# 04_EEPROM_FLASH.net
KiCad netlist of a schematic drawn in Altium Designer
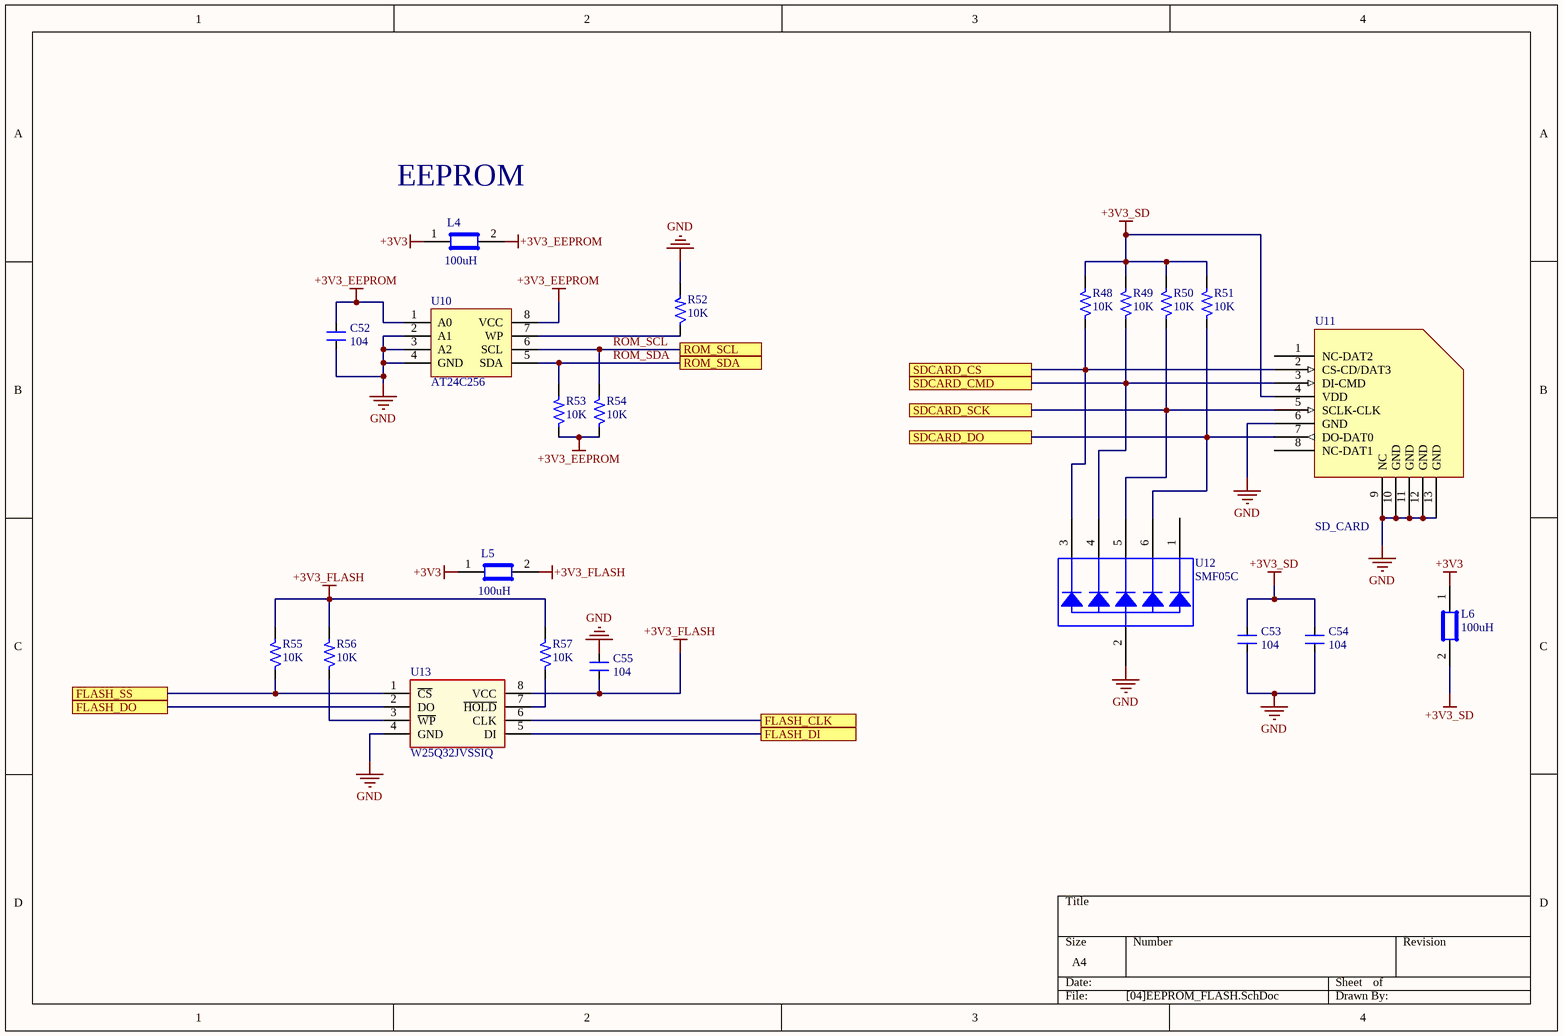
[diagram p0: [04]EEPROM_FLASH.SchDoc]

(export (version "E")
  (design (tool "Eeschema 10.0.6"))
  (components
    (comp (ref "C52")
      (value "104")
      (footprint "C0603 SMT")
      (description "Cap SMD")
      (libsource (lib "GPS_Traking_V1_1") (part "CM"))
    )
    (comp (ref "C53")
      (value "104")
      (footprint "C0603 SMT")
      (description "Cap SMD")
      (libsource (lib "GPS_Traking_V1_1") (part "CM"))
    )
    (comp (ref "C54")
      (value "104")
      (footprint "C0603 SMT")
      (description "Cap SMD")
      (libsource (lib "GPS_Traking_V1_1") (part "CM"))
    )
    (comp (ref "C55")
      (value "104")
      (footprint "C0603 SMT")
      (description "Cap SMD")
      (libsource (lib "GPS_Traking_V1_1") (part "CM"))
    )
    (comp (ref "L4")
      (value "100uH")
      (footprint "R0805")
      (description "100uH 0805")
      (libsource (lib "GPS_Traking_V1_1") (part "Ferrite Bead"))
    )
    (comp (ref "L5")
      (value "100uH")
      (footprint "R0805")
      (description "100uH 0805")
      (libsource (lib "GPS_Traking_V1_1") (part "Ferrite Bead"))
    )
    (comp (ref "L6")
      (value "100uH")
      (footprint "R0805")
      (description "100uH 0805")
      (libsource (lib "GPS_Traking_V1_1") (part "Ferrite Bead"))
    )
    (comp (ref "R48")
      (value "10K")
      (footprint "R0603 -SMT")
      (description "Resistor SMD")
      (libsource (lib "GPS_Traking_V1_1") (part "RM"))
    )
    (comp (ref "R49")
      (value "10K")
      (footprint "R0603 -SMT")
      (description "Resistor SMD")
      (libsource (lib "GPS_Traking_V1_1") (part "RM"))
    )
    (comp (ref "R50")
      (value "10K")
      (footprint "R0603 -SMT")
      (description "Resistor SMD")
      (libsource (lib "GPS_Traking_V1_1") (part "RM"))
    )
    (comp (ref "R51")
      (value "10K")
      (footprint "R0603 -SMT")
      (description "Resistor SMD")
      (libsource (lib "GPS_Traking_V1_1") (part "RM"))
    )
    (comp (ref "R52")
      (value "10K")
      (footprint "R0603 -SMT")
      (description "Resistor SMD")
      (libsource (lib "GPS_Traking_V1_1") (part "RM"))
    )
    (comp (ref "R53")
      (value "10K")
      (footprint "R0603 -SMT")
      (description "Resistor SMD")
      (libsource (lib "GPS_Traking_V1_1") (part "RM"))
    )
    (comp (ref "R54")
      (value "10K")
      (footprint "R0603 -SMT")
      (description "Resistor SMD")
      (libsource (lib "GPS_Traking_V1_1") (part "RM"))
    )
    (comp (ref "R55")
      (value "10K")
      (footprint "R0603 -SMT")
      (description "Resistor SMD")
      (libsource (lib "GPS_Traking_V1_1") (part "RM"))
    )
    (comp (ref "R56")
      (value "10K")
      (footprint "R0603 -SMT")
      (description "Resistor SMD")
      (libsource (lib "GPS_Traking_V1_1") (part "RM"))
    )
    (comp (ref "R57")
      (value "10K")
      (footprint "R0603 -SMT")
      (description "Resistor SMD")
      (libsource (lib "GPS_Traking_V1_1") (part "RM"))
    )
    (comp (ref "U10")
      (value "AT24C256")
      (footprint "SO-8")
      (libsource (lib "GPS_Traking_V1_1") (part "AT24Cxx"))
    )
    (comp (ref "U11")
      (value "SD_CARD")
      (footprint "MICROSD2")
      (description "SD/MMC holder")
      (libsource (lib "My Library") (part "MicroSD"))
    )
    (comp (ref "U12")
      (value "SMF05C")
      (footprint "SOT_363_6")
      (description "ESD Protection")
      (libsource (lib "GPS_Traking_V1_1") (part "SMF05C"))
    )
    (comp (ref "U13")
      (value "W25Q32JVSSIQ")
      (footprint "SO-8 208")
      (description "FLASH 32MBIT 133MHZ 8SOP")
      (libsource (lib "GPS_Traking_V1_1") (part "W25Q32JV"))
    )
  )
  (nets
    (net (code "1") (name "+3V3") (class "Default")
      (node (ref "L4") (pin "1") (pinfunction "1_1") (pintype "passive"))
      (node (ref "L5") (pin "1") (pinfunction "1_1") (pintype "passive"))
      (node (ref "L6") (pin "1") (pinfunction "1_1") (pintype "passive"))
    )
    (net (code "2") (name "+3V3_EEPROM") (class "Default")
      (node (ref "C52") (pin "2") (pinfunction "2_2") (pintype "passive"))
      (node (ref "L4") (pin "2") (pinfunction "2_2") (pintype "passive"))
      (node (ref "R53") (pin "1") (pinfunction "1_1") (pintype "passive"))
      (node (ref "R54") (pin "1") (pinfunction "1_1") (pintype "passive"))
      (node (ref "U10") (pin "1") (pinfunction "A0_1") (pintype "passive"))
      (node (ref "U10") (pin "8") (pinfunction "VCC_8") (pintype "passive"))
    )
    (net (code "3") (name "+3V3_FLASH") (class "Default")
      (node (ref "C55") (pin "1") (pinfunction "1_1") (pintype "passive"))
      (node (ref "L5") (pin "2") (pinfunction "2_2") (pintype "passive"))
      (node (ref "R55") (pin "2") (pinfunction "2_2") (pintype "passive"))
      (node (ref "R56") (pin "2") (pinfunction "2_2") (pintype "passive"))
      (node (ref "R57") (pin "2") (pinfunction "2_2") (pintype "passive"))
      (node (ref "U13") (pin "8") (pinfunction "VCC_8") (pintype "passive"))
    )
    (net (code "4") (name "+3V3_SD") (class "Default")
      (node (ref "C53") (pin "2") (pinfunction "2_2") (pintype "passive"))
      (node (ref "C54") (pin "2") (pinfunction "2_2") (pintype "passive"))
      (node (ref "L6") (pin "2") (pinfunction "2_2") (pintype "passive"))
      (node (ref "R48") (pin "2") (pinfunction "2_2") (pintype "passive"))
      (node (ref "R49") (pin "2") (pinfunction "2_2") (pintype "passive"))
      (node (ref "R50") (pin "2") (pinfunction "2_2") (pintype "passive"))
      (node (ref "R51") (pin "2") (pinfunction "2_2") (pintype "passive"))
      (node (ref "U11") (pin "4") (pinfunction "VDD_4") (pintype "passive"))
    )
    (net (code "5") (name "/FLASH_CLK") (class "Default")
      (node (ref "U13") (pin "6") (pinfunction "CLK_6") (pintype "passive"))
    )
    (net (code "6") (name "/FLASH_DI") (class "Default")
      (node (ref "U13") (pin "5") (pinfunction "DI_5") (pintype "passive"))
    )
    (net (code "7") (name "/FLASH_DO") (class "Default")
      (node (ref "U13") (pin "2") (pinfunction "DO_2") (pintype "passive"))
    )
    (net (code "8") (name "/FLASH_SS") (class "Default")
      (node (ref "R55") (pin "1") (pinfunction "1_1") (pintype "passive"))
      (node (ref "U13") (pin "1") (pinfunction "~{CS}_1") (pintype "passive"))
    )
    (net (code "9") (name "/ROM_SCL") (class "Default")
      (node (ref "R54") (pin "2") (pinfunction "2_2") (pintype "passive"))
      (node (ref "U10") (pin "6") (pinfunction "SCL_6") (pintype "passive"))
    )
    (net (code "10") (name "/ROM_SDA") (class "Default")
      (node (ref "R53") (pin "2") (pinfunction "2_2") (pintype "passive"))
      (node (ref "U10") (pin "5") (pinfunction "SDA_5") (pintype "passive"))
    )
    (net (code "11") (name "/SDCARD_CMD") (class "Default")
      (node (ref "R49") (pin "1") (pinfunction "1_1") (pintype "passive"))
      (node (ref "U11") (pin "3") (pinfunction "DI-CMD_3") (pintype "input"))
      (node (ref "U12") (pin "4") (pinfunction "K3_4") (pintype "passive"))
    )
    (net (code "12") (name "/SDCARD_CS") (class "Default")
      (node (ref "R48") (pin "1") (pinfunction "1_1") (pintype "passive"))
      (node (ref "U11") (pin "2") (pinfunction "CS-CD/DAT3_2") (pintype "input"))
      (node (ref "U12") (pin "3") (pinfunction "K2_3") (pintype "passive"))
    )
    (net (code "13") (name "/SDCARD_DO") (class "Default")
      (node (ref "R51") (pin "1") (pinfunction "1_1") (pintype "passive"))
      (node (ref "U11") (pin "7") (pinfunction "DO-DAT0_7") (pintype "output"))
      (node (ref "U12") (pin "6") (pinfunction "K5_6") (pintype "passive"))
    )
    (net (code "14") (name "/SDCARD_SCK") (class "Default")
      (node (ref "R50") (pin "1") (pinfunction "1_1") (pintype "passive"))
      (node (ref "U11") (pin "5") (pinfunction "SCLK-CLK_5") (pintype "input"))
      (node (ref "U12") (pin "5") (pinfunction "K4_5") (pintype "power_in"))
    )
    (net (code "15") (name "GND") (class "Default")
      (node (ref "C52") (pin "1") (pinfunction "1_1") (pintype "passive"))
      (node (ref "C53") (pin "1") (pinfunction "1_1") (pintype "passive"))
      (node (ref "C54") (pin "1") (pinfunction "1_1") (pintype "passive"))
      (node (ref "C55") (pin "2") (pinfunction "2_2") (pintype "passive"))
      (node (ref "R52") (pin "2") (pinfunction "2_2") (pintype "passive"))
      (node (ref "U10") (pin "2") (pinfunction "A1_2") (pintype "passive"))
      (node (ref "U10") (pin "3") (pinfunction "A2_3") (pintype "passive"))
      (node (ref "U10") (pin "4") (pinfunction "GND_4") (pintype "passive"))
      (node (ref "U11") (pin "10") (pinfunction "GND_10") (pintype "passive"))
      (node (ref "U11") (pin "11") (pinfunction "GND_11") (pintype "passive"))
      (node (ref "U11") (pin "12") (pinfunction "GND_12") (pintype "passive"))
      (node (ref "U11") (pin "13") (pinfunction "GND_13") (pintype "passive"))
      (node (ref "U11") (pin "6") (pinfunction "GND_6") (pintype "passive"))
      (node (ref "U11") (pin "9") (pinfunction "NC_9") (pintype "passive"))
      (node (ref "U12") (pin "2") (pinfunction "A_2") (pintype "power_in"))
      (node (ref "U13") (pin "4") (pinfunction "GND_4") (pintype "passive"))
    )
    (net (code "16") (name "Net-(U10-WP)") (class "Default")
      (node (ref "R52") (pin "1") (pinfunction "1_1") (pintype "passive"))
      (node (ref "U10") (pin "7") (pinfunction "WP_7") (pintype "passive"))
    )
    (net (code "17") (name "Net-(U13-~{HOLD})") (class "Default")
      (node (ref "R57") (pin "1") (pinfunction "1_1") (pintype "passive"))
      (node (ref "U13") (pin "7") (pinfunction "~{HOLD}_7") (pintype "passive"))
    )
    (net (code "18") (name "Net-(U13-~{WP})") (class "Default")
      (node (ref "R56") (pin "1") (pinfunction "1_1") (pintype "passive"))
      (node (ref "U13") (pin "3") (pinfunction "~{WP}_3") (pintype "passive"))
    )
    (net (code "19") (name "unconnected-(U11-NC-DAT1-Pad8)") (class "Default")
      (node (ref "U11") (pin "8") (pinfunction "NC-DAT1_8") (pintype "passive"))
    )
    (net (code "20") (name "unconnected-(U11-NC-DAT2-Pad1)") (class "Default")
      (node (ref "U11") (pin "1") (pinfunction "NC-DAT2_1") (pintype "passive"))
    )
    (net (code "21") (name "unconnected-(U12-K1-Pad1)") (class "Default")
      (node (ref "U12") (pin "1") (pinfunction "K1_1") (pintype "passive"))
    )
  )
)
